# ClockClock_Main_X40.net
KiCad netlist of a schematic drawn in EAGLE
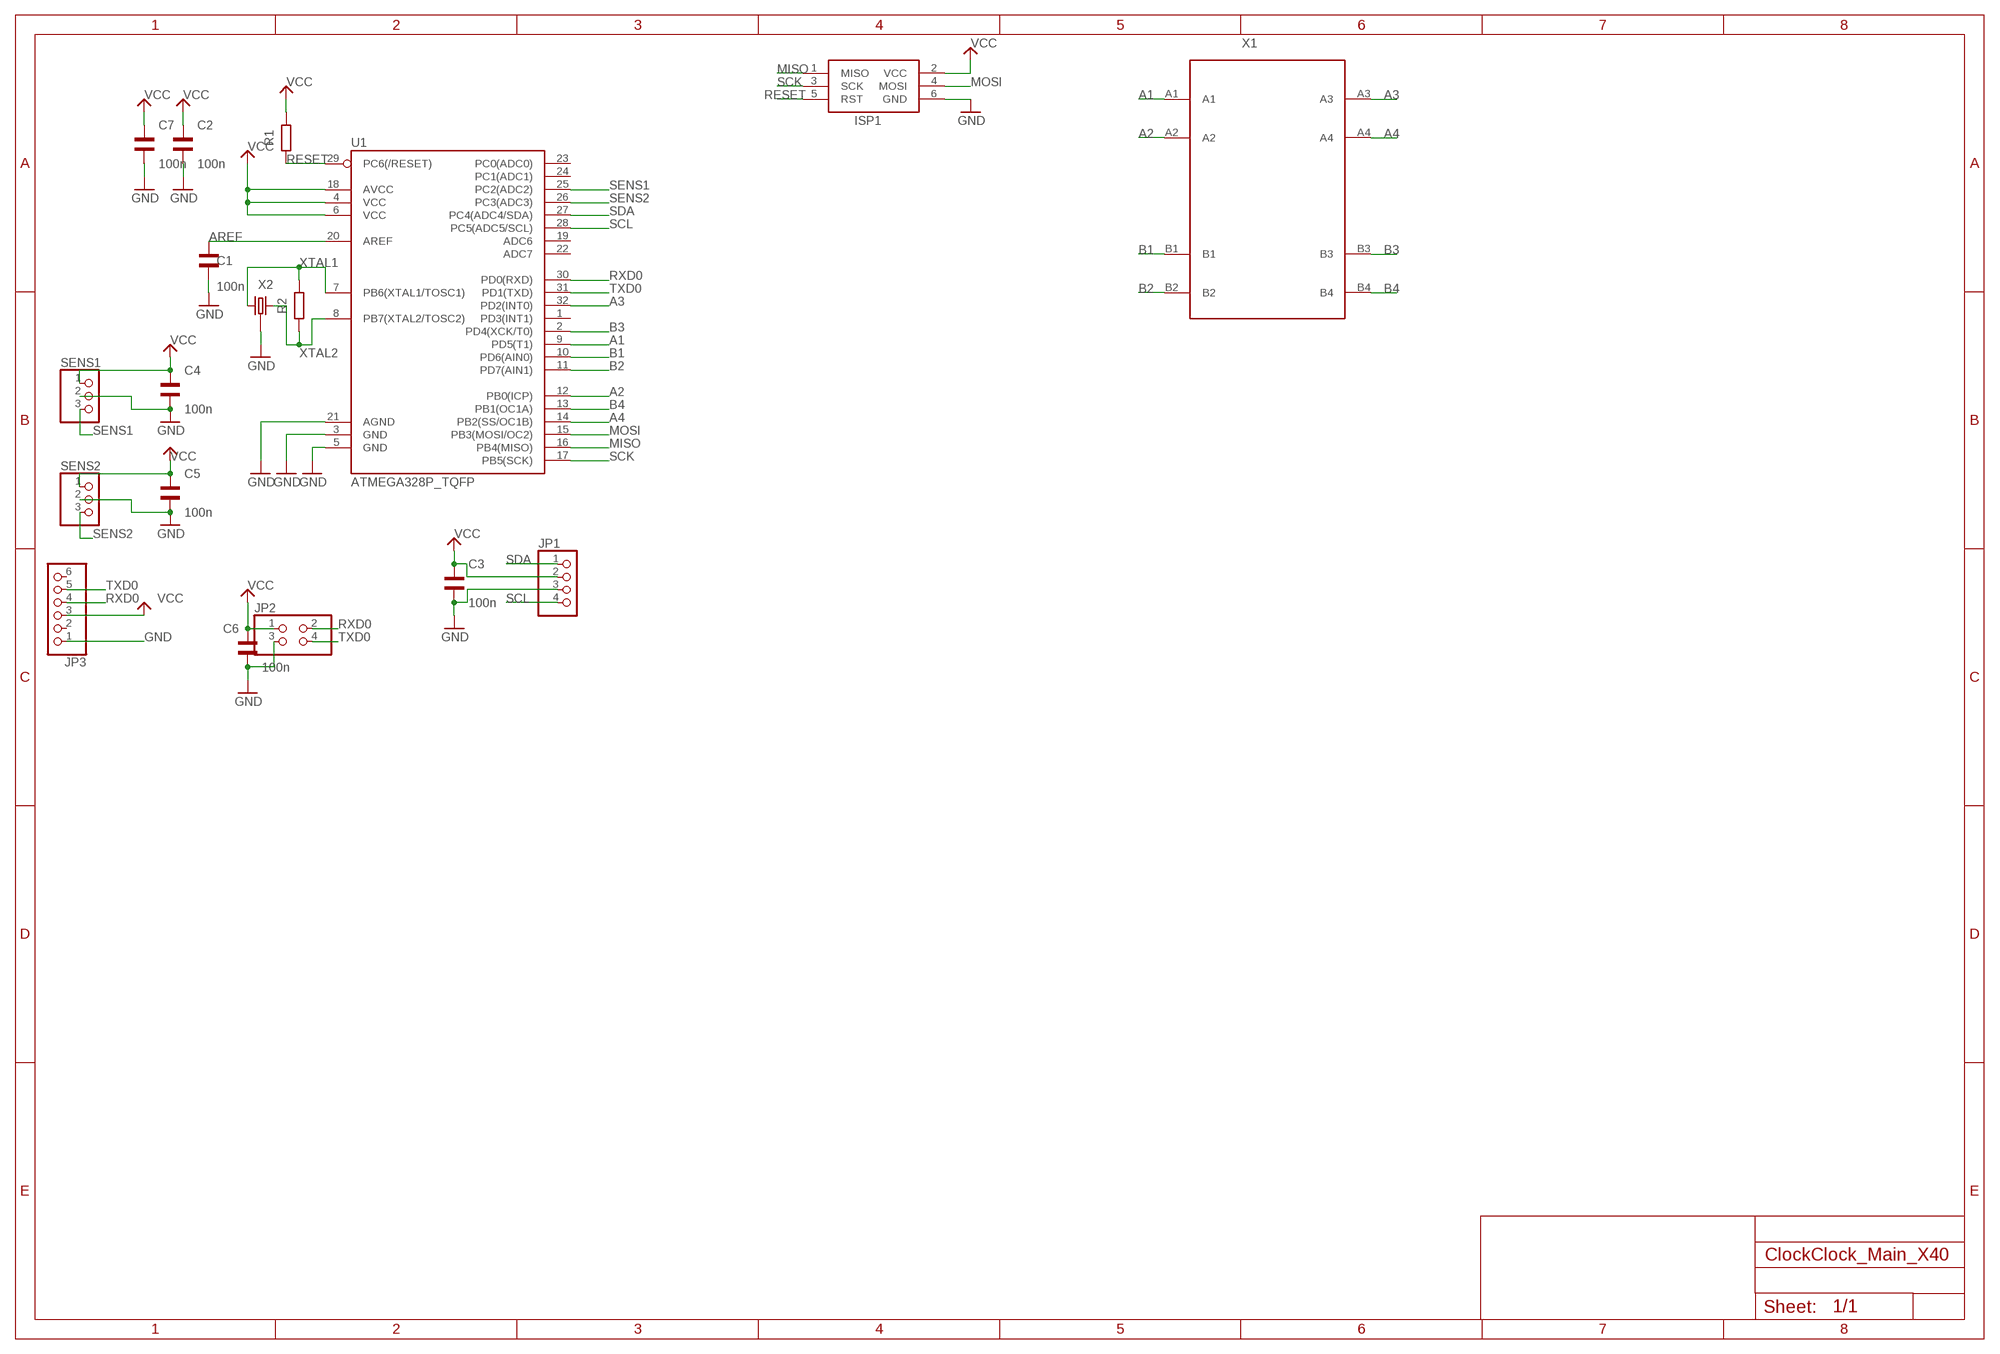
[diagram p0: schematic, sheet 1]

(export (version "E")
  (design (tool "Eeschema 10.0.6"))
  (components
    (comp (ref "C1")
      (value "100n")
      (footprint "eagle-import:WCAP-CSMH_1206_WAVE")
      (libsource (lib "eagle-import") (part "WCAP-CSMH_1206_WAVE_885342208002"))
    )
    (comp (ref "C2")
      (value "100n")
      (footprint "eagle-import:WCAP-CSMH_1206_WAVE")
      (libsource (lib "eagle-import") (part "WCAP-CSMH_1206_WAVE_885342208002"))
    )
    (comp (ref "C3")
      (value "100n")
      (footprint "eagle-import:WCAP-CSMH_1206_WAVE")
      (libsource (lib "eagle-import") (part "WCAP-CSMH_1206_WAVE_885342208002"))
    )
    (comp (ref "C4")
      (value "100n")
      (footprint "eagle-import:WCAP-CSMH_1206_WAVE")
      (libsource (lib "eagle-import") (part "WCAP-CSMH_1206_WAVE_885342208002"))
    )
    (comp (ref "C5")
      (value "100n")
      (footprint "eagle-import:WCAP-CSMH_1206_WAVE")
      (libsource (lib "eagle-import") (part "WCAP-CSMH_1206_WAVE_885342208002"))
    )
    (comp (ref "C6")
      (value "100n")
      (footprint "eagle-import:WCAP-CSMH_1206_WAVE")
      (libsource (lib "eagle-import") (part "WCAP-CSMH_1206_WAVE_885342208002"))
    )
    (comp (ref "C7")
      (value "100n")
      (footprint "eagle-import:WCAP-CSMH_1206_WAVE")
      (libsource (lib "eagle-import") (part "WCAP-CSMH_1206_WAVE_885342208002"))
    )
    (comp (ref "ISP1")
      (value "AVRISP-6")
      (footprint "eagle-import:AVRISP")
      (libsource (lib "eagle-import") (part "AVRISP-6"))
    )
    (comp (ref "JP1")
      (value "PINHD-1X4/90")
      (footprint "eagle-import:1X04_90")
      (libsource (lib "eagle-import") (part "PINHD-1X4/90"))
    )
    (comp (ref "JP2")
      (value "PINHD-2X2")
      (footprint "eagle-import:2X02")
      (libsource (lib "eagle-import") (part "PINHD-2X2"))
    )
    (comp (ref "JP3")
      (value "PINHD-1X6")
      (footprint "eagle-import:1X06")
      (libsource (lib "eagle-import") (part "PINHD-1X6"))
    )
    (comp (ref "R1")
      (value "15k")
      (footprint "eagle-import:R1206")
      (libsource (lib "eagle-import") (part "R-EU_R1206"))
    )
    (comp (ref "R2")
      (value "1M")
      (footprint "eagle-import:R0805")
      (libsource (lib "eagle-import") (part "R-EU_R0805"))
    )
    (comp (ref "SENS1")
      (value "PINHD-1X3")
      (footprint "eagle-import:1X03")
      (libsource (lib "eagle-import") (part "PINHD-1X3"))
    )
    (comp (ref "SENS2")
      (value "PINHD-1X3")
      (footprint "eagle-import:1X03")
      (libsource (lib "eagle-import") (part "PINHD-1X3"))
    )
    (comp (ref "U1")
      (value "ATMEGA328P_TQFP")
      (footprint "eagle-import:TQFP32-08")
      (libsource (lib "eagle-import") (part "ATMEGA328P_TQFP"))
    )
    (comp (ref "X1")
      (value "X40_MOTOR")
      (footprint "eagle-import:X40_MOTOR")
      (libsource (lib "eagle-import") (part "X40_MOTOR"))
    )
    (comp (ref "X2")
      (value "AEL_ZTT_RESONATOR_16M")
      (footprint "eagle-import:AEL_ZTT_RESONATOR")
      (libsource (lib "eagle-import") (part "AEL_ZTT_RESONATOR_16M"))
    )
  )
  (nets
    (net (code "1") (name "/A1") (class "Default")
      (node (ref "U1") (pin "9") (pinfunction "PD5(T1)_9") (pintype "bidirectional"))
      (node (ref "X1") (pin "A1") (pinfunction "A1_A1") (pintype "bidirectional"))
    )
    (net (code "2") (name "/A2") (class "Default")
      (node (ref "U1") (pin "12") (pinfunction "PB0(ICP)_12") (pintype "bidirectional"))
      (node (ref "X1") (pin "A2") (pinfunction "A2_A2") (pintype "bidirectional"))
    )
    (net (code "3") (name "/A3") (class "Default")
      (node (ref "U1") (pin "32") (pinfunction "PD2(INT0)_32") (pintype "bidirectional"))
      (node (ref "X1") (pin "A3") (pinfunction "A3_A3") (pintype "bidirectional"))
    )
    (net (code "4") (name "/A4") (class "Default")
      (node (ref "U1") (pin "14") (pinfunction "PB2(SS/OC1B)_14") (pintype "bidirectional"))
      (node (ref "X1") (pin "A4") (pinfunction "A4_A4") (pintype "bidirectional"))
    )
    (net (code "5") (name "/AREF") (class "Default")
      (node (ref "C1") (pin "2") (pinfunction "2_2") (pintype "passive"))
      (node (ref "U1") (pin "20") (pinfunction "AREF_20") (pintype "bidirectional"))
    )
    (net (code "6") (name "/B1") (class "Default")
      (node (ref "U1") (pin "10") (pinfunction "PD6(AIN0)_10") (pintype "bidirectional"))
      (node (ref "X1") (pin "B1") (pinfunction "B1_B1") (pintype "bidirectional"))
    )
    (net (code "7") (name "/B2") (class "Default")
      (node (ref "U1") (pin "11") (pinfunction "PD7(AIN1)_11") (pintype "bidirectional"))
      (node (ref "X1") (pin "B2") (pinfunction "B2_B2") (pintype "bidirectional"))
    )
    (net (code "8") (name "/B3") (class "Default")
      (node (ref "U1") (pin "2") (pinfunction "PD4(XCK/T0)_2") (pintype "bidirectional"))
      (node (ref "X1") (pin "B3") (pinfunction "B3_B3") (pintype "bidirectional"))
    )
    (net (code "9") (name "/B4") (class "Default")
      (node (ref "U1") (pin "13") (pinfunction "PB1(OC1A)_13") (pintype "bidirectional"))
      (node (ref "X1") (pin "B4") (pinfunction "B4_B4") (pintype "bidirectional"))
    )
    (net (code "10") (name "/MISO") (class "Default")
      (node (ref "ISP1") (pin "1") (pinfunction "MISO_1") (pintype "input"))
      (node (ref "U1") (pin "16") (pinfunction "PB4(MISO)_16") (pintype "bidirectional"))
    )
    (net (code "11") (name "/MOSI") (class "Default")
      (node (ref "ISP1") (pin "4") (pinfunction "MOSI_4") (pintype "output"))
      (node (ref "U1") (pin "15") (pinfunction "PB3(MOSI/OC2)_15") (pintype "bidirectional"))
    )
    (net (code "12") (name "/RESET") (class "Default")
      (node (ref "ISP1") (pin "5") (pinfunction "RST_5") (pintype "output"))
      (node (ref "R1") (pin "1") (pinfunction "1_1") (pintype "passive"))
      (node (ref "U1") (pin "29") (pinfunction "PC6(/RESET)_29") (pintype "bidirectional"))
    )
    (net (code "13") (name "/RXD0") (class "Default")
      (node (ref "JP2") (pin "2") (pinfunction "2_2") (pintype "passive"))
      (node (ref "JP3") (pin "4") (pinfunction "4_4") (pintype "passive"))
      (node (ref "U1") (pin "30") (pinfunction "PD0(RXD)_30") (pintype "bidirectional"))
    )
    (net (code "14") (name "/SCK") (class "Default")
      (node (ref "ISP1") (pin "3") (pinfunction "SCK_3") (pintype "output"))
      (node (ref "U1") (pin "17") (pinfunction "PB5(SCK)_17") (pintype "bidirectional"))
    )
    (net (code "15") (name "/SCL") (class "Default")
      (node (ref "JP1") (pin "4") (pinfunction "4_4") (pintype "passive"))
      (node (ref "U1") (pin "28") (pinfunction "PC5(ADC5/SCL)_28") (pintype "bidirectional"))
    )
    (net (code "16") (name "/SDA") (class "Default")
      (node (ref "JP1") (pin "1") (pinfunction "1_1") (pintype "passive"))
      (node (ref "U1") (pin "27") (pinfunction "PC4(ADC4/SDA)_27") (pintype "bidirectional"))
    )
    (net (code "17") (name "/SENS1") (class "Default")
      (node (ref "SENS1") (pin "3") (pinfunction "3_3") (pintype "passive"))
      (node (ref "U1") (pin "25") (pinfunction "PC2(ADC2)_25") (pintype "bidirectional"))
    )
    (net (code "18") (name "/SENS2") (class "Default")
      (node (ref "SENS2") (pin "3") (pinfunction "3_3") (pintype "passive"))
      (node (ref "U1") (pin "26") (pinfunction "PC3(ADC3)_26") (pintype "bidirectional"))
    )
    (net (code "19") (name "/TXD0") (class "Default")
      (node (ref "JP2") (pin "4") (pinfunction "4_4") (pintype "passive"))
      (node (ref "JP3") (pin "5") (pinfunction "5_5") (pintype "passive"))
      (node (ref "U1") (pin "31") (pinfunction "PD1(TXD)_31") (pintype "bidirectional"))
    )
    (net (code "20") (name "/XTAL1") (class "Default")
      (node (ref "R2") (pin "2") (pinfunction "2_2") (pintype "passive"))
      (node (ref "U1") (pin "7") (pinfunction "PB6(XTAL1/TOSC1)_7") (pintype "bidirectional"))
      (node (ref "X2") (pin "P$1") (pinfunction "1_P$1") (pintype "passive"))
    )
    (net (code "21") (name "/XTAL2") (class "Default")
      (node (ref "R2") (pin "1") (pinfunction "1_1") (pintype "passive"))
      (node (ref "U1") (pin "8") (pinfunction "PB7(XTAL2/TOSC2)_8") (pintype "bidirectional"))
      (node (ref "X2") (pin "P$3") (pinfunction "2_P$3") (pintype "passive"))
    )
    (net (code "22") (name "5V") (class "Default")
      (node (ref "C2") (pin "2") (pinfunction "2_2") (pintype "passive"))
      (node (ref "C3") (pin "2") (pinfunction "2_2") (pintype "passive"))
      (node (ref "C4") (pin "2") (pinfunction "2_2") (pintype "passive"))
      (node (ref "C5") (pin "2") (pinfunction "2_2") (pintype "passive"))
      (node (ref "C6") (pin "2") (pinfunction "2_2") (pintype "passive"))
      (node (ref "C7") (pin "2") (pinfunction "2_2") (pintype "passive"))
      (node (ref "ISP1") (pin "2") (pinfunction "VCC_2") (pintype "power_in"))
      (node (ref "JP1") (pin "2") (pinfunction "2_2") (pintype "passive"))
      (node (ref "JP2") (pin "1") (pinfunction "1_1") (pintype "passive"))
      (node (ref "JP3") (pin "3") (pinfunction "3_3") (pintype "passive"))
      (node (ref "R1") (pin "2") (pinfunction "2_2") (pintype "passive"))
      (node (ref "SENS1") (pin "1") (pinfunction "1_1") (pintype "passive"))
      (node (ref "SENS2") (pin "1") (pinfunction "1_1") (pintype "passive"))
      (node (ref "U1") (pin "18") (pinfunction "AVCC_18") (pintype "bidirectional"))
      (node (ref "U1") (pin "4") (pinfunction "VCC_4") (pintype "bidirectional"))
      (node (ref "U1") (pin "6") (pinfunction "VCC_6") (pintype "bidirectional"))
    )
    (net (code "23") (name "GND") (class "Default")
      (node (ref "C1") (pin "1") (pinfunction "1_1") (pintype "passive"))
      (node (ref "C2") (pin "1") (pinfunction "1_1") (pintype "passive"))
      (node (ref "C3") (pin "1") (pinfunction "1_1") (pintype "passive"))
      (node (ref "C4") (pin "1") (pinfunction "1_1") (pintype "passive"))
      (node (ref "C5") (pin "1") (pinfunction "1_1") (pintype "passive"))
      (node (ref "C6") (pin "1") (pinfunction "1_1") (pintype "passive"))
      (node (ref "C7") (pin "1") (pinfunction "1_1") (pintype "passive"))
      (node (ref "ISP1") (pin "6") (pinfunction "GND_6") (pintype "power_in"))
      (node (ref "JP1") (pin "3") (pinfunction "3_3") (pintype "passive"))
      (node (ref "JP2") (pin "3") (pinfunction "3_3") (pintype "passive"))
      (node (ref "JP3") (pin "1") (pinfunction "1_1") (pintype "passive"))
      (node (ref "SENS1") (pin "2") (pinfunction "2_2") (pintype "passive"))
      (node (ref "SENS2") (pin "2") (pinfunction "2_2") (pintype "passive"))
      (node (ref "U1") (pin "21") (pinfunction "AGND_21") (pintype "bidirectional"))
      (node (ref "U1") (pin "3") (pinfunction "GND_3") (pintype "bidirectional"))
      (node (ref "U1") (pin "5") (pinfunction "GND_5") (pintype "bidirectional"))
      (node (ref "X2") (pin "GND") (pinfunction "GND_GND") (pintype "passive"))
    )
    (net (code "24") (name "unconnected-(JP3-Pad2)") (class "Default")
      (node (ref "JP3") (pin "2") (pinfunction "2_2") (pintype "passive"))
    )
    (net (code "25") (name "unconnected-(JP3-Pad6)") (class "Default")
      (node (ref "JP3") (pin "6") (pinfunction "6_6") (pintype "passive"))
    )
    (net (code "26") (name "unconnected-(U1-ADC6-Pad19)") (class "Default")
      (node (ref "U1") (pin "19") (pinfunction "ADC6_19") (pintype "bidirectional"))
    )
    (net (code "27") (name "unconnected-(U1-ADC7-Pad22)") (class "Default")
      (node (ref "U1") (pin "22") (pinfunction "ADC7_22") (pintype "bidirectional"))
    )
    (net (code "28") (name "unconnected-(U1-PC0(ADC0)-Pad23)") (class "Default")
      (node (ref "U1") (pin "23") (pinfunction "PC0(ADC0)_23") (pintype "bidirectional"))
    )
    (net (code "29") (name "unconnected-(U1-PC1(ADC1)-Pad24)") (class "Default")
      (node (ref "U1") (pin "24") (pinfunction "PC1(ADC1)_24") (pintype "bidirectional"))
    )
    (net (code "30") (name "unconnected-(U1-PD3(INT1)-Pad1)") (class "Default")
      (node (ref "U1") (pin "1") (pinfunction "PD3(INT1)_1") (pintype "bidirectional"))
    )
  )
)
